# Main.net
KiCad netlist of a schematic drawn in EAGLE
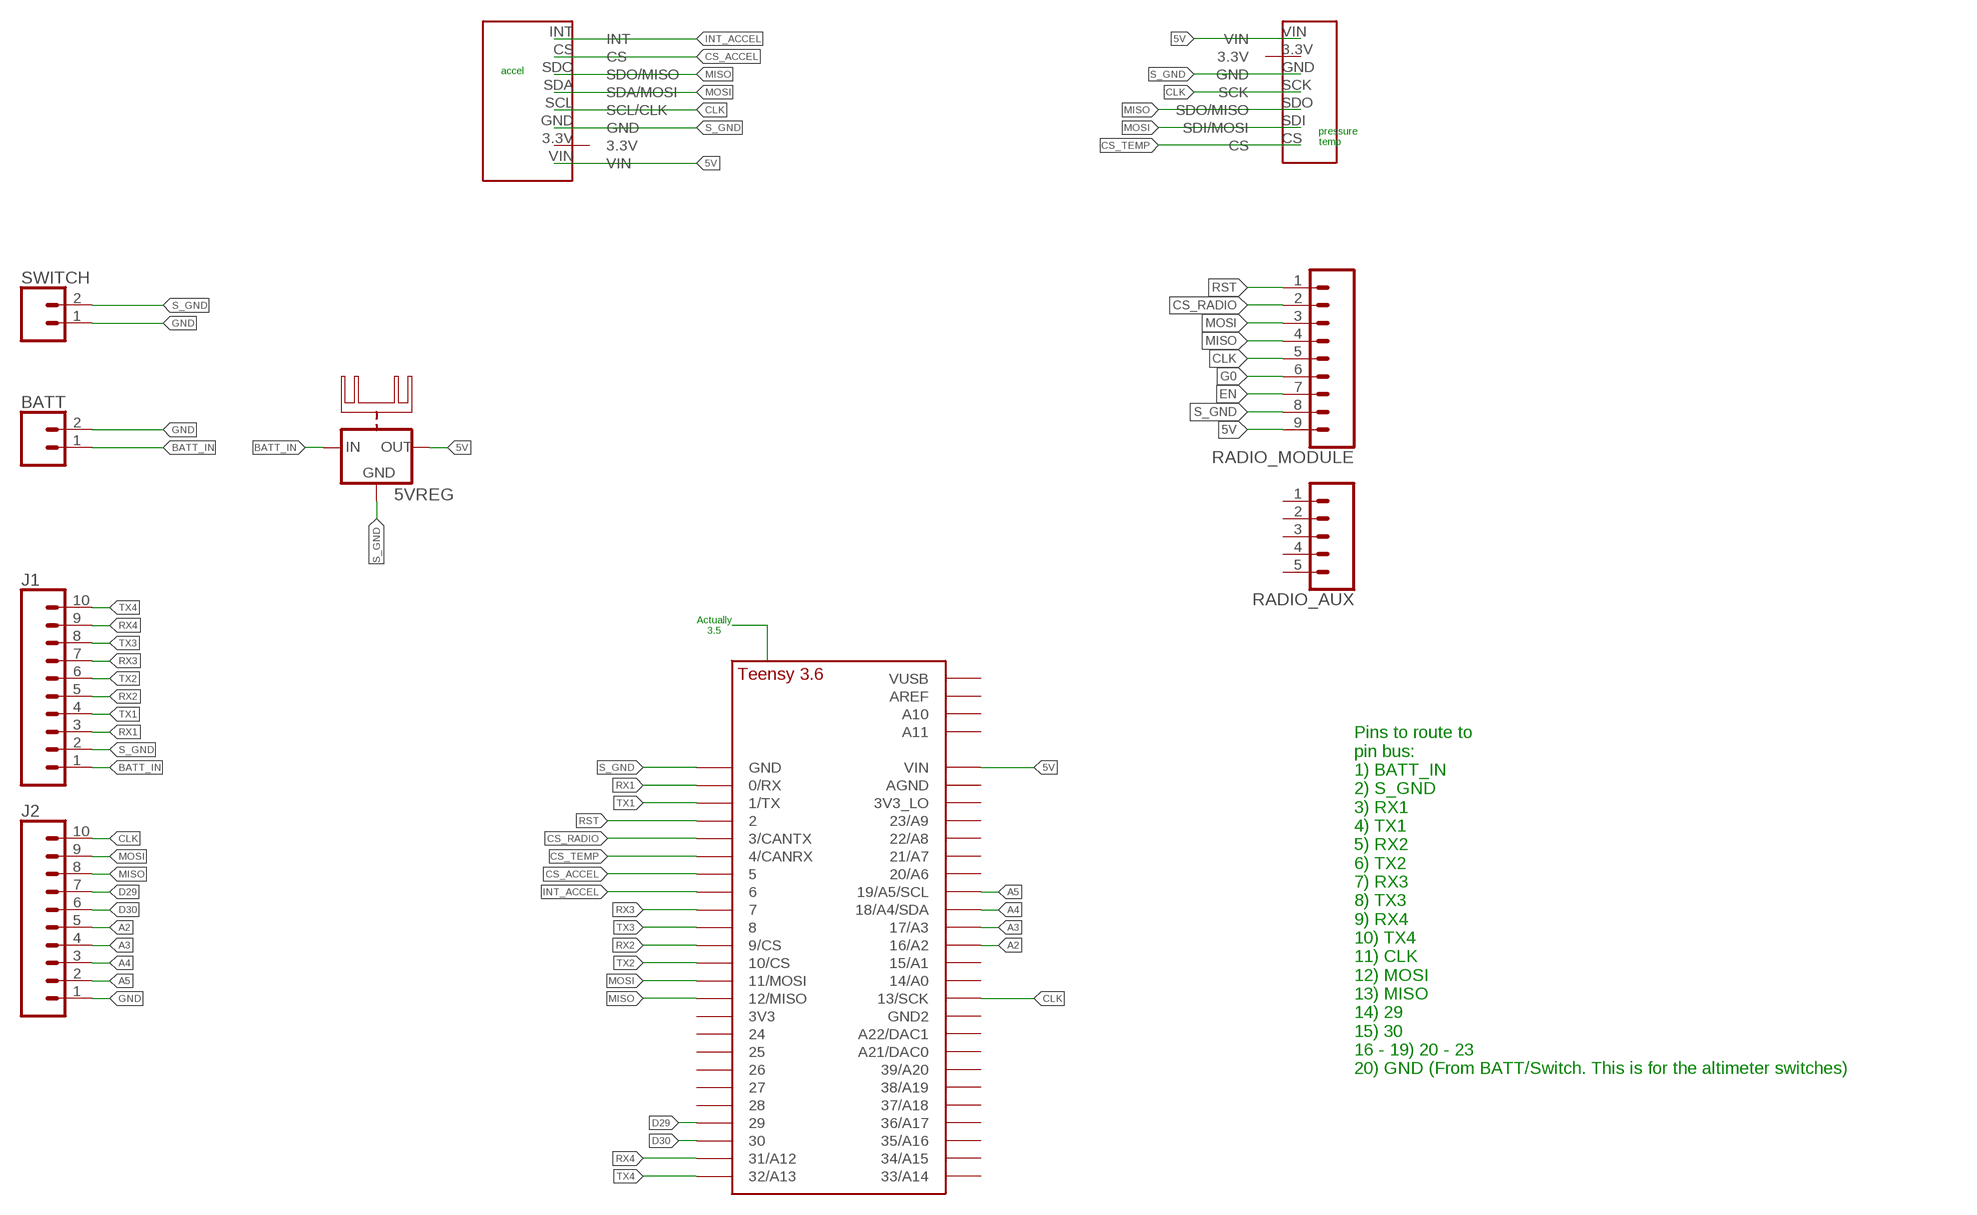
[diagram p0: schematic, sheet 1]

(export (version "E")
  (design (tool "Eeschema 10.0.6"))
  (components
    (comp (ref "5VREG")
      (value "78XXH")
      (footprint "eagle-import:78XXH")
      (libsource (lib "eagle-import") (part "78XXH"))
    )
    (comp (ref "BATT")
      (value "CONN_02-JST-2-PTH-NO_SILK")
      (footprint "eagle-import:JST-2-PTH-NS")
      (libsource (lib "eagle-import") (part "CONN_02-JST-2-PTH-NO_SILK"))
    )
    (comp (ref "J1")
      (value "CONN_10\"")
      (footprint "eagle-import:1X10")
      (libsource (lib "eagle-import") (part "CONN_10{dblquote}"))
    )
    (comp (ref "J2")
      (value "CONN_10\"")
      (footprint "eagle-import:1X10")
      (libsource (lib "eagle-import") (part "CONN_10{dblquote}"))
    )
    (comp (ref "RADIO_AUX")
      (value "CONN_05")
      (footprint "eagle-import:1X05")
      (libsource (lib "eagle-import") (part "CONN_05"))
    )
    (comp (ref "RADIO_MODULE")
      (value "CONN_09")
      (footprint "eagle-import:1X09")
      (libsource (lib "eagle-import") (part "CONN_09"))
    )
    (comp (ref "SWITCH")
      (value "CONN_02-JST-2-PTH-NO_SILK")
      (footprint "eagle-import:JST-2-PTH-NS")
      (libsource (lib "eagle-import") (part "CONN_02-JST-2-PTH-NO_SILK"))
    )
    (comp (ref "U$1")
      (value "TEENSY_3.5/3.6_BASIC")
      (footprint "eagle-import:TEENSY_3.5_3.6_BASIC")
      (libsource (lib "eagle-import") (part "TEENSY_3.5/3.6_BASIC"))
    )
    (comp (ref "U$2")
      (value "LIS3DH")
      (footprint "eagle-import:LIS3DH")
      (libsource (lib "eagle-import") (part "LIS3DH"))
    )
    (comp (ref "U$3")
      (value "BMP280")
      (footprint "eagle-import:BMP280")
      (libsource (lib "eagle-import") (part "BMP280"))
    )
  )
  (nets
    (net (code "1") (name "5V") (class "Default")
      (node (ref "5VREG") (pin "OUT") (pinfunction "OUT_OUT") (pintype "passive"))
      (node (ref "RADIO_MODULE") (pin "9") (pinfunction "9_9") (pintype "passive"))
      (node (ref "U$1") (pin "VIN") (pinfunction "VIN_VIN") (pintype "bidirectional"))
      (node (ref "U$2") (pin "VIN") (pinfunction "VIN_VIN") (pintype "bidirectional"))
      (node (ref "U$3") (pin "VIN") (pinfunction "VIN_VIN") (pintype "bidirectional"))
    )
    (net (code "2") (name "A2") (class "Default")
      (node (ref "J2") (pin "5") (pinfunction "5_5") (pintype "passive"))
      (node (ref "U$1") (pin "16/A2") (pinfunction "16/A2_16/A2") (pintype "bidirectional"))
    )
    (net (code "3") (name "A3") (class "Default")
      (node (ref "J2") (pin "4") (pinfunction "4_4") (pintype "passive"))
      (node (ref "U$1") (pin "17/A3") (pinfunction "17/A3_17/A3") (pintype "bidirectional"))
    )
    (net (code "4") (name "A4") (class "Default")
      (node (ref "J2") (pin "3") (pinfunction "3_3") (pintype "passive"))
      (node (ref "U$1") (pin "18/A4/SDA") (pinfunction "18/A4/SDA_18/A4/SDA") (pintype "bidirectional"))
    )
    (net (code "5") (name "A5") (class "Default")
      (node (ref "J2") (pin "2") (pinfunction "2_2") (pintype "passive"))
      (node (ref "U$1") (pin "19/A5/SCL") (pinfunction "19/A5/SCL_19/A5/SCL") (pintype "bidirectional"))
    )
    (net (code "6") (name "BATT_IN") (class "Default")
      (node (ref "5VREG") (pin "IN") (pinfunction "IN_IN") (pintype "input"))
      (node (ref "BATT") (pin "1") (pinfunction "1_1") (pintype "passive"))
      (node (ref "J1") (pin "1") (pinfunction "1_1") (pintype "passive"))
    )
    (net (code "7") (name "CLK") (class "Default")
      (node (ref "J2") (pin "10") (pinfunction "10_10") (pintype "passive"))
      (node (ref "RADIO_MODULE") (pin "5") (pinfunction "5_5") (pintype "passive"))
      (node (ref "U$1") (pin "13/SCK") (pinfunction "13/SCK_13/SCK") (pintype "bidirectional"))
      (node (ref "U$2") (pin "SCL") (pinfunction "SCL/CLK_SCL") (pintype "bidirectional"))
      (node (ref "U$3") (pin "SCK") (pinfunction "SCK_SCK") (pintype "bidirectional"))
    )
    (net (code "8") (name "CS_ACCEL") (class "Default")
      (node (ref "U$1") (pin "5") (pinfunction "5_5") (pintype "bidirectional"))
      (node (ref "U$2") (pin "CS") (pinfunction "CS_CS") (pintype "bidirectional"))
    )
    (net (code "9") (name "CS_RADIO") (class "Default")
      (node (ref "RADIO_MODULE") (pin "2") (pinfunction "2_2") (pintype "passive"))
      (node (ref "U$1") (pin "3/CANTX") (pinfunction "3/CANTX_3/CANTX") (pintype "bidirectional"))
    )
    (net (code "10") (name "CS_TEMP") (class "Default")
      (node (ref "U$1") (pin "4/CANRX") (pinfunction "4/CANRX_4/CANRX") (pintype "bidirectional"))
      (node (ref "U$3") (pin "CS") (pinfunction "CS_CS") (pintype "bidirectional"))
    )
    (net (code "11") (name "D29") (class "Default")
      (node (ref "J2") (pin "7") (pinfunction "7_7") (pintype "passive"))
      (node (ref "U$1") (pin "29") (pinfunction "29_29") (pintype "bidirectional"))
    )
    (net (code "12") (name "D30") (class "Default")
      (node (ref "J2") (pin "6") (pinfunction "6_6") (pintype "passive"))
      (node (ref "U$1") (pin "30") (pinfunction "30_30") (pintype "bidirectional"))
    )
    (net (code "13") (name "EN") (class "Default")
      (node (ref "RADIO_MODULE") (pin "7") (pinfunction "7_7") (pintype "passive"))
    )
    (net (code "14") (name "G0") (class "Default")
      (node (ref "RADIO_MODULE") (pin "6") (pinfunction "6_6") (pintype "passive"))
    )
    (net (code "15") (name "GND") (class "Default")
      (node (ref "BATT") (pin "2") (pinfunction "2_2") (pintype "passive"))
      (node (ref "J2") (pin "1") (pinfunction "1_1") (pintype "passive"))
      (node (ref "SWITCH") (pin "1") (pinfunction "1_1") (pintype "passive"))
    )
    (net (code "16") (name "INT_ACCEL") (class "Default")
      (node (ref "U$1") (pin "6") (pinfunction "6_6") (pintype "bidirectional"))
      (node (ref "U$2") (pin "INT") (pinfunction "INT_INT") (pintype "bidirectional"))
    )
    (net (code "17") (name "MISO") (class "Default")
      (node (ref "J2") (pin "8") (pinfunction "8_8") (pintype "passive"))
      (node (ref "RADIO_MODULE") (pin "4") (pinfunction "4_4") (pintype "passive"))
      (node (ref "U$1") (pin "12/MISO") (pinfunction "12/MISO_12/MISO") (pintype "bidirectional"))
      (node (ref "U$2") (pin "SDO") (pinfunction "SDO/MISO_SDO") (pintype "bidirectional"))
      (node (ref "U$3") (pin "SDO") (pinfunction "SDO/MISO_SDO") (pintype "bidirectional"))
    )
    (net (code "18") (name "MOSI") (class "Default")
      (node (ref "J2") (pin "9") (pinfunction "9_9") (pintype "passive"))
      (node (ref "RADIO_MODULE") (pin "3") (pinfunction "3_3") (pintype "passive"))
      (node (ref "U$1") (pin "11/MOSI") (pinfunction "11/MOSI_11/MOSI") (pintype "bidirectional"))
      (node (ref "U$2") (pin "SDA") (pinfunction "SDA/MOSI_SDA") (pintype "bidirectional"))
      (node (ref "U$3") (pin "SDI") (pinfunction "SDI/MOSI_SDI") (pintype "bidirectional"))
    )
    (net (code "19") (name "RST") (class "Default")
      (node (ref "RADIO_MODULE") (pin "1") (pinfunction "1_1") (pintype "passive"))
      (node (ref "U$1") (pin "2") (pinfunction "2_2") (pintype "bidirectional"))
    )
    (net (code "20") (name "RX1") (class "Default")
      (node (ref "J1") (pin "3") (pinfunction "3_3") (pintype "passive"))
      (node (ref "U$1") (pin "0/RX") (pinfunction "0/RX_0/RX") (pintype "bidirectional"))
    )
    (net (code "21") (name "RX2") (class "Default")
      (node (ref "J1") (pin "5") (pinfunction "5_5") (pintype "passive"))
      (node (ref "U$1") (pin "9/CS") (pinfunction "9/CS_9/CS") (pintype "bidirectional"))
    )
    (net (code "22") (name "RX3") (class "Default")
      (node (ref "J1") (pin "7") (pinfunction "7_7") (pintype "passive"))
      (node (ref "U$1") (pin "7") (pinfunction "7_7") (pintype "bidirectional"))
    )
    (net (code "23") (name "RX4") (class "Default")
      (node (ref "J1") (pin "9") (pinfunction "9_9") (pintype "passive"))
      (node (ref "U$1") (pin "31/A12") (pinfunction "31/A12_31/A12") (pintype "bidirectional"))
    )
    (net (code "24") (name "S_GND") (class "Default")
      (node (ref "5VREG") (pin "GND") (pinfunction "GND_GND") (pintype "input"))
      (node (ref "J1") (pin "2") (pinfunction "2_2") (pintype "passive"))
      (node (ref "RADIO_MODULE") (pin "8") (pinfunction "8_8") (pintype "passive"))
      (node (ref "SWITCH") (pin "2") (pinfunction "2_2") (pintype "passive"))
      (node (ref "U$1") (pin "GND") (pinfunction "GND_GND") (pintype "bidirectional"))
      (node (ref "U$2") (pin "GND") (pinfunction "GND_GND") (pintype "bidirectional"))
      (node (ref "U$3") (pin "GND") (pinfunction "GND_GND") (pintype "bidirectional"))
    )
    (net (code "25") (name "TX1") (class "Default")
      (node (ref "J1") (pin "4") (pinfunction "4_4") (pintype "passive"))
      (node (ref "U$1") (pin "1/TX") (pinfunction "1/TX_1/TX") (pintype "bidirectional"))
    )
    (net (code "26") (name "TX2") (class "Default")
      (node (ref "J1") (pin "6") (pinfunction "6_6") (pintype "passive"))
      (node (ref "U$1") (pin "10/CS") (pinfunction "10/CS_10/CS") (pintype "bidirectional"))
    )
    (net (code "27") (name "TX3") (class "Default")
      (node (ref "J1") (pin "8") (pinfunction "8_8") (pintype "passive"))
      (node (ref "U$1") (pin "8") (pinfunction "8_8") (pintype "bidirectional"))
    )
    (net (code "28") (name "TX4") (class "Default")
      (node (ref "J1") (pin "10") (pinfunction "10_10") (pintype "passive"))
      (node (ref "U$1") (pin "32/A13") (pinfunction "32/A13_32/A13") (pintype "bidirectional"))
    )
    (net (code "29") (name "unconnected-(RADIO_AUX-Pad1)") (class "Default")
      (node (ref "RADIO_AUX") (pin "1") (pinfunction "1_1") (pintype "passive"))
    )
    (net (code "30") (name "unconnected-(RADIO_AUX-Pad2)") (class "Default")
      (node (ref "RADIO_AUX") (pin "2") (pinfunction "2_2") (pintype "passive"))
    )
    (net (code "31") (name "unconnected-(RADIO_AUX-Pad3)") (class "Default")
      (node (ref "RADIO_AUX") (pin "3") (pinfunction "3_3") (pintype "passive"))
    )
    (net (code "32") (name "unconnected-(RADIO_AUX-Pad4)") (class "Default")
      (node (ref "RADIO_AUX") (pin "4") (pinfunction "4_4") (pintype "passive"))
    )
    (net (code "33") (name "unconnected-(RADIO_AUX-Pad5)") (class "Default")
      (node (ref "RADIO_AUX") (pin "5") (pinfunction "5_5") (pintype "passive"))
    )
    (net (code "34") (name "unconnected-(U$1-A21{slash}DAC0-Pad21{slash}DAC0)") (class "Default")
      (node (ref "U$1") (pin "21/DAC0") (pinfunction "A21/DAC0_21/DAC0") (pintype "bidirectional"))
    )
    (net (code "35") (name "unconnected-(U$1-Pad3V3)") (class "Default")
      (node (ref "U$1") (pin "3V3") (pinfunction "3V3_3V3") (pintype "bidirectional"))
    )
    (net (code "36") (name "unconnected-(U$1-Pad3V3_LO)") (class "Default")
      (node (ref "U$1") (pin "3V3_LO") (pinfunction "3V3_LO_3V3_LO") (pintype "bidirectional"))
    )
    (net (code "37") (name "unconnected-(U$1-Pad14{slash}A0)") (class "Default")
      (node (ref "U$1") (pin "14/A0") (pinfunction "14/A0_14/A0") (pintype "bidirectional"))
    )
    (net (code "38") (name "unconnected-(U$1-Pad15{slash}A1)") (class "Default")
      (node (ref "U$1") (pin "15/A1") (pinfunction "15/A1_15/A1") (pintype "bidirectional"))
    )
    (net (code "39") (name "unconnected-(U$1-Pad20{slash}A6)") (class "Default")
      (node (ref "U$1") (pin "20/A6") (pinfunction "20/A6_20/A6") (pintype "bidirectional"))
    )
    (net (code "40") (name "unconnected-(U$1-Pad21{slash}A7)") (class "Default")
      (node (ref "U$1") (pin "21/A7") (pinfunction "21/A7_21/A7") (pintype "bidirectional"))
    )
    (net (code "41") (name "unconnected-(U$1-Pad22{slash}A8)") (class "Default")
      (node (ref "U$1") (pin "22/A8") (pinfunction "22/A8_22/A8") (pintype "bidirectional"))
    )
    (net (code "42") (name "unconnected-(U$1-Pad23{slash}A9)") (class "Default")
      (node (ref "U$1") (pin "23/A9") (pinfunction "23/A9_23/A9") (pintype "bidirectional"))
    )
    (net (code "43") (name "unconnected-(U$1-Pad24)") (class "Default")
      (node (ref "U$1") (pin "24") (pinfunction "24_24") (pintype "bidirectional"))
    )
    (net (code "44") (name "unconnected-(U$1-Pad25)") (class "Default")
      (node (ref "U$1") (pin "25") (pinfunction "25_25") (pintype "bidirectional"))
    )
    (net (code "45") (name "unconnected-(U$1-Pad26)") (class "Default")
      (node (ref "U$1") (pin "26") (pinfunction "26_26") (pintype "bidirectional"))
    )
    (net (code "46") (name "unconnected-(U$1-Pad27)") (class "Default")
      (node (ref "U$1") (pin "27") (pinfunction "27_27") (pintype "bidirectional"))
    )
    (net (code "47") (name "unconnected-(U$1-Pad28)") (class "Default")
      (node (ref "U$1") (pin "28") (pinfunction "28_28") (pintype "bidirectional"))
    )
    (net (code "48") (name "unconnected-(U$1-Pad33{slash}A14)") (class "Default")
      (node (ref "U$1") (pin "33/A14") (pinfunction "33/A14_33/A14") (pintype "bidirectional"))
    )
    (net (code "49") (name "unconnected-(U$1-Pad34{slash}A15)") (class "Default")
      (node (ref "U$1") (pin "34/A15") (pinfunction "34/A15_34/A15") (pintype "bidirectional"))
    )
    (net (code "50") (name "unconnected-(U$1-Pad35{slash}A16)") (class "Default")
      (node (ref "U$1") (pin "35/A16") (pinfunction "35/A16_35/A16") (pintype "bidirectional"))
    )
    (net (code "51") (name "unconnected-(U$1-Pad36{slash}A17)") (class "Default")
      (node (ref "U$1") (pin "36/A17") (pinfunction "36/A17_36/A17") (pintype "bidirectional"))
    )
    (net (code "52") (name "unconnected-(U$1-Pad37{slash}A18)") (class "Default")
      (node (ref "U$1") (pin "37/A18") (pinfunction "37/A18_37/A18") (pintype "bidirectional"))
    )
    (net (code "53") (name "unconnected-(U$1-Pad38{slash}A19)") (class "Default")
      (node (ref "U$1") (pin "38/A19") (pinfunction "38/A19_38/A19") (pintype "bidirectional"))
    )
    (net (code "54") (name "unconnected-(U$1-Pad39{slash}A20)") (class "Default")
      (node (ref "U$1") (pin "39/A20") (pinfunction "39/A20_39/A20") (pintype "bidirectional"))
    )
    (net (code "55") (name "unconnected-(U$1-PadA10)") (class "Default")
      (node (ref "U$1") (pin "A10") (pinfunction "A10_A10") (pintype "bidirectional"))
    )
    (net (code "56") (name "unconnected-(U$1-PadA11)") (class "Default")
      (node (ref "U$1") (pin "A11") (pinfunction "A11_A11") (pintype "bidirectional"))
    )
    (net (code "57") (name "unconnected-(U$1-PadA22{slash}DAC1)") (class "Default")
      (node (ref "U$1") (pin "A22/DAC1") (pinfunction "A22/DAC1_A22/DAC1") (pintype "bidirectional"))
    )
    (net (code "58") (name "unconnected-(U$1-PadAGND)") (class "Default")
      (node (ref "U$1") (pin "AGND") (pinfunction "AGND_AGND") (pintype "bidirectional"))
    )
    (net (code "59") (name "unconnected-(U$1-PadAREF)") (class "Default")
      (node (ref "U$1") (pin "AREF") (pinfunction "AREF_AREF") (pintype "bidirectional"))
    )
    (net (code "60") (name "unconnected-(U$1-PadGND2)") (class "Default")
      (node (ref "U$1") (pin "GND2") (pinfunction "GND2_GND2") (pintype "bidirectional"))
    )
    (net (code "61") (name "unconnected-(U$1-PadVUSB)") (class "Default")
      (node (ref "U$1") (pin "VUSB") (pinfunction "VUSB_VUSB") (pintype "bidirectional"))
    )
    (net (code "62") (name "unconnected-(U$2-Pad3.3V)") (class "Default")
      (node (ref "U$2") (pin "3.3V") (pinfunction "3.3V_3.3V") (pintype "bidirectional"))
    )
    (net (code "63") (name "unconnected-(U$3-Pad3.3V)") (class "Default")
      (node (ref "U$3") (pin "3.3V") (pinfunction "3.3V_3.3V") (pintype "bidirectional"))
    )
  )
)
